# Apex_CV_Expander_3U_UI_v1_0.net
KiCad netlist of a schematic drawn in EAGLE
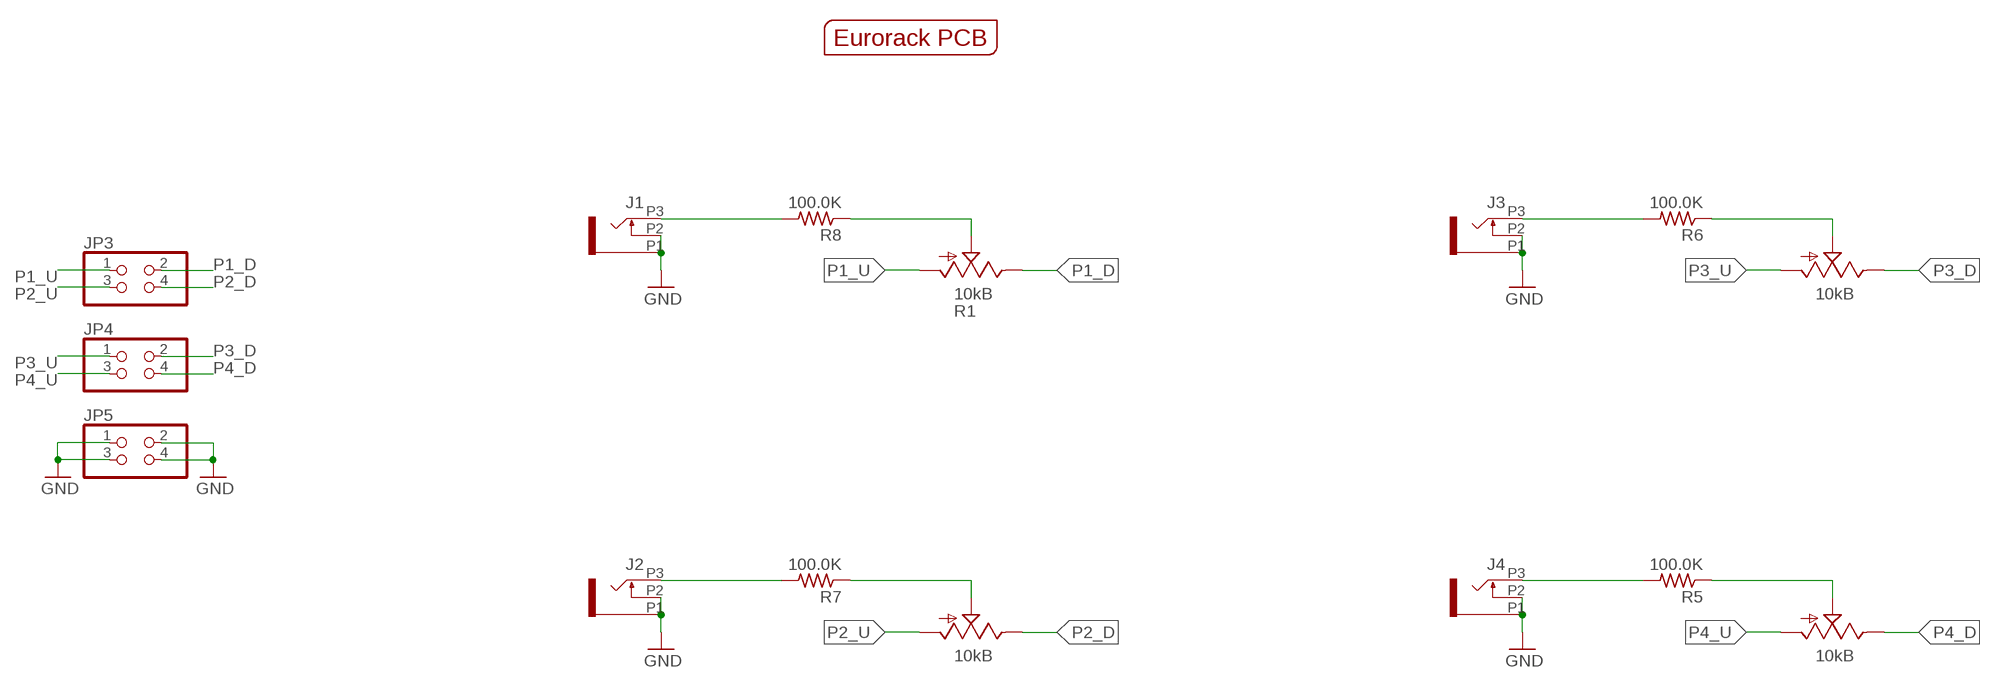
[diagram p0: schematic, sheet 1]

(export (version "E")
  (design (tool "Eeschema 10.0.6"))
  (components
    (comp (ref "J1")
      (value "OG-PJ301_PJ301_THONKICONN7")
      (footprint "eagle-import:OG-PJ301_WQP_PJ_301M7")
      (libsource (lib "eagle-import") (part "OG-PJ301_PJ301_THONKICONN7"))
    )
    (comp (ref "J2")
      (value "OG-PJ301_PJ301_THONKICONN7")
      (footprint "eagle-import:OG-PJ301_WQP_PJ_301M7")
      (libsource (lib "eagle-import") (part "OG-PJ301_PJ301_THONKICONN7"))
    )
    (comp (ref "J3")
      (value "OG-PJ301_PJ301_THONKICONN7")
      (footprint "eagle-import:OG-PJ301_WQP_PJ_301M7")
      (libsource (lib "eagle-import") (part "OG-PJ301_PJ301_THONKICONN7"))
    )
    (comp (ref "J4")
      (value "OG-PJ301_PJ301_THONKICONN7")
      (footprint "eagle-import:OG-PJ301_WQP_PJ_301M7")
      (libsource (lib "eagle-import") (part "OG-PJ301_PJ301_THONKICONN7"))
    )
    (comp (ref "JP3")
      (value "PINHD-2X2")
      (footprint "eagle-import:2X02")
      (libsource (lib "eagle-import") (part "PINHD-2X2"))
    )
    (comp (ref "JP4")
      (value "PINHD-2X2")
      (footprint "eagle-import:2X02")
      (libsource (lib "eagle-import") (part "PINHD-2X2"))
    )
    (comp (ref "JP5")
      (value "PINHD-2X2")
      (footprint "eagle-import:2X02")
      (libsource (lib "eagle-import") (part "PINHD-2X2"))
    )
    (comp (ref "PCB1")
      (value "EURORACK_PCB2HP")
      (footprint "eagle-import:EURORACK2HPPCB")
      (libsource (lib "eagle-import") (part "EURORACK_PCB2HP"))
    )
    (comp (ref "R1")
      (value "10kB")
      (footprint "eagle-import:POTS_TALL_TRIMMER_POT_VERTICAL_SLOTED")
      (libsource (lib "eagle-import") (part "POTS_POT_USSLOTED_TALL_TRIMMER"))
    )
    (comp (ref "R2")
      (value "10kB")
      (footprint "eagle-import:POTS_TALL_TRIMMER_POT_VERTICAL_SLOTED")
      (libsource (lib "eagle-import") (part "POTS_POT_USSLOTED_TALL_TRIMMER"))
    )
    (comp (ref "R3")
      (value "10kB")
      (footprint "eagle-import:POTS_TALL_TRIMMER_POT_VERTICAL_SLOTED")
      (libsource (lib "eagle-import") (part "POTS_POT_USSLOTED_TALL_TRIMMER"))
    )
    (comp (ref "R4")
      (value "10kB")
      (footprint "eagle-import:POTS_TALL_TRIMMER_POT_VERTICAL_SLOTED")
      (libsource (lib "eagle-import") (part "POTS_POT_USSLOTED_TALL_TRIMMER"))
    )
    (comp (ref "R5")
      (value "100.0K")
      (footprint "eagle-import:R0603")
      (libsource (lib "eagle-import") (part "R-US_R0603"))
    )
    (comp (ref "R6")
      (value "100.0K")
      (footprint "eagle-import:R0603")
      (libsource (lib "eagle-import") (part "R-US_R0603"))
    )
    (comp (ref "R7")
      (value "100.0K")
      (footprint "eagle-import:R0603")
      (libsource (lib "eagle-import") (part "R-US_R0603"))
    )
    (comp (ref "R8")
      (value "100.0K")
      (footprint "eagle-import:R0603")
      (libsource (lib "eagle-import") (part "R-US_R0603"))
    )
  )
  (nets
    (net (code "1") (name "GND") (class "Default")
      (node (ref "J1") (pin "P1") (pinfunction "1_P1") (pintype "passive"))
      (node (ref "J1") (pin "P2") (pinfunction "2_P2") (pintype "passive"))
      (node (ref "J2") (pin "P1") (pinfunction "1_P1") (pintype "passive"))
      (node (ref "J2") (pin "P2") (pinfunction "2_P2") (pintype "passive"))
      (node (ref "J3") (pin "P1") (pinfunction "1_P1") (pintype "passive"))
      (node (ref "J3") (pin "P2") (pinfunction "2_P2") (pintype "passive"))
      (node (ref "J4") (pin "P1") (pinfunction "1_P1") (pintype "passive"))
      (node (ref "J4") (pin "P2") (pinfunction "2_P2") (pintype "passive"))
      (node (ref "JP5") (pin "1") (pinfunction "1_1") (pintype "passive"))
      (node (ref "JP5") (pin "2") (pinfunction "2_2") (pintype "passive"))
      (node (ref "JP5") (pin "3") (pinfunction "3_3") (pintype "passive"))
      (node (ref "JP5") (pin "4") (pinfunction "4_4") (pintype "passive"))
    )
    (net (code "2") (name "Net-(J1-3)") (class "Default")
      (node (ref "J1") (pin "P3") (pinfunction "3_P3") (pintype "passive"))
      (node (ref "R8") (pin "2") (pinfunction "2_2") (pintype "passive"))
    )
    (net (code "3") (name "Net-(J2-3)") (class "Default")
      (node (ref "J2") (pin "P3") (pinfunction "3_P3") (pintype "passive"))
      (node (ref "R7") (pin "2") (pinfunction "2_2") (pintype "passive"))
    )
    (net (code "4") (name "Net-(J3-3)") (class "Default")
      (node (ref "J3") (pin "P3") (pinfunction "3_P3") (pintype "passive"))
      (node (ref "R6") (pin "2") (pinfunction "2_2") (pintype "passive"))
    )
    (net (code "5") (name "Net-(J4-3)") (class "Default")
      (node (ref "J4") (pin "P3") (pinfunction "3_P3") (pintype "passive"))
      (node (ref "R5") (pin "2") (pinfunction "2_2") (pintype "passive"))
    )
    (net (code "6") (name "Net-(R1-S)") (class "Default")
      (node (ref "R1") (pin "P$2") (pinfunction "S_P$2") (pintype "passive"))
      (node (ref "R8") (pin "1") (pinfunction "1_1") (pintype "passive"))
    )
    (net (code "7") (name "Net-(R2-S)") (class "Default")
      (node (ref "R2") (pin "P$2") (pinfunction "S_P$2") (pintype "passive"))
      (node (ref "R7") (pin "1") (pinfunction "1_1") (pintype "passive"))
    )
    (net (code "8") (name "Net-(R3-S)") (class "Default")
      (node (ref "R3") (pin "P$2") (pinfunction "S_P$2") (pintype "passive"))
      (node (ref "R6") (pin "1") (pinfunction "1_1") (pintype "passive"))
    )
    (net (code "9") (name "Net-(R4-S)") (class "Default")
      (node (ref "R4") (pin "P$2") (pinfunction "S_P$2") (pintype "passive"))
      (node (ref "R5") (pin "1") (pinfunction "1_1") (pintype "passive"))
    )
    (net (code "10") (name "P1_D") (class "Default")
      (node (ref "JP3") (pin "2") (pinfunction "2_2") (pintype "passive"))
      (node (ref "R1") (pin "P$1") (pinfunction "E_P$1") (pintype "passive"))
    )
    (net (code "11") (name "P1_U") (class "Default")
      (node (ref "JP3") (pin "1") (pinfunction "1_1") (pintype "passive"))
      (node (ref "R1") (pin "P$3") (pinfunction "A_P$3") (pintype "passive"))
    )
    (net (code "12") (name "P2_D") (class "Default")
      (node (ref "JP3") (pin "4") (pinfunction "4_4") (pintype "passive"))
      (node (ref "R2") (pin "P$1") (pinfunction "E_P$1") (pintype "passive"))
    )
    (net (code "13") (name "P2_U") (class "Default")
      (node (ref "JP3") (pin "3") (pinfunction "3_3") (pintype "passive"))
      (node (ref "R2") (pin "P$3") (pinfunction "A_P$3") (pintype "passive"))
    )
    (net (code "14") (name "P3_D") (class "Default")
      (node (ref "JP4") (pin "2") (pinfunction "2_2") (pintype "passive"))
      (node (ref "R3") (pin "P$1") (pinfunction "E_P$1") (pintype "passive"))
    )
    (net (code "15") (name "P3_U") (class "Default")
      (node (ref "JP4") (pin "1") (pinfunction "1_1") (pintype "passive"))
      (node (ref "R3") (pin "P$3") (pinfunction "A_P$3") (pintype "passive"))
    )
    (net (code "16") (name "P4_D") (class "Default")
      (node (ref "JP4") (pin "4") (pinfunction "4_4") (pintype "passive"))
      (node (ref "R4") (pin "P$1") (pinfunction "E_P$1") (pintype "passive"))
    )
    (net (code "17") (name "P4_U") (class "Default")
      (node (ref "JP4") (pin "3") (pinfunction "3_3") (pintype "passive"))
      (node (ref "R4") (pin "P$3") (pinfunction "A_P$3") (pintype "passive"))
    )
  )
)
